# SCH_Power_Jack.net
KiCad netlist of a schematic drawn in Altium Designer
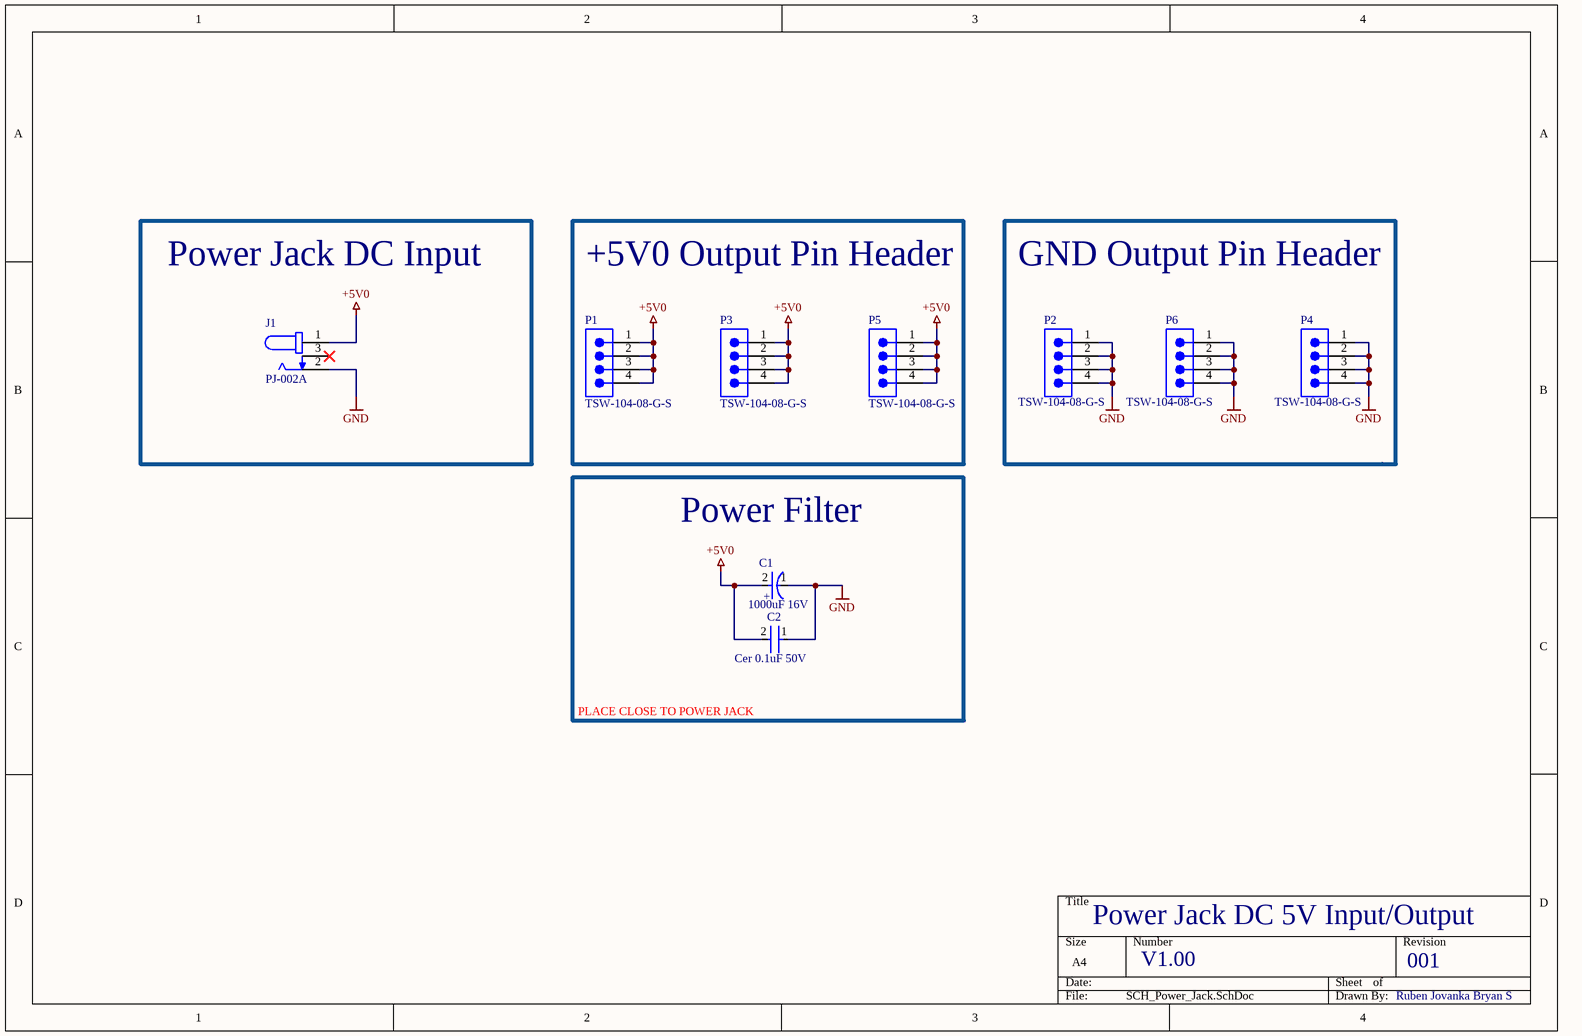
[diagram p0: SCH_Power_Jack.SchDoc]

(export (version "E")
  (design (tool "Eeschema 10.0.6"))
  (components
    (comp (ref "C1")
      (value "1000uF 16V")
      (footprint "FP-OS-CON-SMT-F10-MFG")
      (description "CAP ALUM POLY 1000UF 20% 16V SMD")
      (libsource (lib "Altium Content Vault") (part "203bc49f2ac43e59fd269a8c329ed05"))
    )
    (comp (ref "C2")
      (value "Cer 0.1uF 50V")
      (footprint "FP-K15H5-MFG")
      (description "CAP CER 0.1UF 50V X7R RADIAL")
      (fields (field (name "TOLERANCE") "10%") (field (name "VOLTAGE") "50V"))
      (libsource (lib "Altium Content Vault") (part "02cd4be3c70576c341d710602a673aa"))
    )
    (comp (ref "J1")
      (value "PJ-002A")
      (footprint "CUI_PJ-002A")
      (description "2.0 x 6.5 mm, 2.5 A, Horizontal, Through Hole, Dc Power Jack Connector")
      (fields (field (name "MF") "Same Sky"))
      (libsource (lib "PJ-002A") (part "PJ-002A"))
    )
    (comp (ref "P1")
      (value "TSW-104-08-G-S")
      (footprint "SMTC-TSW-104-08-X-S")
      (description "0.025\" SQ Post Header, Through-hole, Vertical, -55 to 125 degC, 2.54 mm Pitch, 4-Pin, Male, RoHS")
      (fields (field (name "MANUFACTURER") "Samtec"))
      (libsource (lib "Altium Content Vault") (part "SMTC-TSW-104-08-X-S"))
    )
    (comp (ref "P2")
      (value "TSW-104-08-G-S")
      (footprint "SMTC-TSW-104-08-X-S")
      (description "0.025\" SQ Post Header, Through-hole, Vertical, -55 to 125 degC, 2.54 mm Pitch, 4-Pin, Male, RoHS")
      (fields (field (name "MANUFACTURER") "Samtec"))
      (libsource (lib "Altium Content Vault") (part "SMTC-TSW-104-08-X-S"))
    )
    (comp (ref "P3")
      (value "TSW-104-08-G-S")
      (footprint "SMTC-TSW-104-08-X-S")
      (description "0.025\" SQ Post Header, Through-hole, Vertical, -55 to 125 degC, 2.54 mm Pitch, 4-Pin, Male, RoHS")
      (fields (field (name "MANUFACTURER") "Samtec"))
      (libsource (lib "Altium Content Vault") (part "SMTC-TSW-104-08-X-S"))
    )
    (comp (ref "P4")
      (value "TSW-104-08-G-S")
      (footprint "SMTC-TSW-104-08-X-S")
      (description "0.025\" SQ Post Header, Through-hole, Vertical, -55 to 125 degC, 2.54 mm Pitch, 4-Pin, Male, RoHS")
      (fields (field (name "MANUFACTURER") "Samtec"))
      (libsource (lib "Altium Content Vault") (part "SMTC-TSW-104-08-X-S"))
    )
    (comp (ref "P5")
      (value "TSW-104-08-G-S")
      (footprint "SMTC-TSW-104-08-X-S")
      (description "0.025\" SQ Post Header, Through-hole, Vertical, -55 to 125 degC, 2.54 mm Pitch, 4-Pin, Male, RoHS")
      (fields (field (name "MANUFACTURER") "Samtec"))
      (libsource (lib "Altium Content Vault") (part "SMTC-TSW-104-08-X-S"))
    )
    (comp (ref "P6")
      (value "TSW-104-08-G-S")
      (footprint "SMTC-TSW-104-08-X-S")
      (description "0.025\" SQ Post Header, Through-hole, Vertical, -55 to 125 degC, 2.54 mm Pitch, 4-Pin, Male, RoHS")
      (fields (field (name "MANUFACTURER") "Samtec"))
      (libsource (lib "Altium Content Vault") (part "SMTC-TSW-104-08-X-S"))
    )
  )
  (nets
    (net (code "1") (name "+5V0") (class "Default")
      (node (ref "C1") (pin "2") (pinfunction "A_2") (pintype "passive"))
      (node (ref "C2") (pin "2") (pinfunction "2_2") (pintype "passive"))
      (node (ref "J1") (pin "1") (pinfunction "1_1") (pintype "passive"))
      (node (ref "P1") (pin "1") (pinfunction "1_1") (pintype "passive"))
      (node (ref "P1") (pin "2") (pinfunction "2_2") (pintype "passive"))
      (node (ref "P1") (pin "3") (pinfunction "3_3") (pintype "passive"))
      (node (ref "P1") (pin "4") (pinfunction "4_4") (pintype "passive"))
      (node (ref "P3") (pin "1") (pinfunction "1_1") (pintype "passive"))
      (node (ref "P3") (pin "2") (pinfunction "2_2") (pintype "passive"))
      (node (ref "P3") (pin "3") (pinfunction "3_3") (pintype "passive"))
      (node (ref "P3") (pin "4") (pinfunction "4_4") (pintype "passive"))
      (node (ref "P5") (pin "1") (pinfunction "1_1") (pintype "passive"))
      (node (ref "P5") (pin "2") (pinfunction "2_2") (pintype "passive"))
      (node (ref "P5") (pin "3") (pinfunction "3_3") (pintype "passive"))
      (node (ref "P5") (pin "4") (pinfunction "4_4") (pintype "passive"))
    )
    (net (code "2") (name "GND") (class "Default")
      (node (ref "C1") (pin "1") (pinfunction "C_1") (pintype "passive"))
      (node (ref "C2") (pin "1") (pinfunction "1_1") (pintype "passive"))
      (node (ref "J1") (pin "2") (pinfunction "2_2") (pintype "passive"))
      (node (ref "P2") (pin "1") (pinfunction "1_1") (pintype "passive"))
      (node (ref "P2") (pin "2") (pinfunction "2_2") (pintype "passive"))
      (node (ref "P2") (pin "3") (pinfunction "3_3") (pintype "passive"))
      (node (ref "P2") (pin "4") (pinfunction "4_4") (pintype "passive"))
      (node (ref "P4") (pin "1") (pinfunction "1_1") (pintype "passive"))
      (node (ref "P4") (pin "2") (pinfunction "2_2") (pintype "passive"))
      (node (ref "P4") (pin "3") (pinfunction "3_3") (pintype "passive"))
      (node (ref "P4") (pin "4") (pinfunction "4_4") (pintype "passive"))
      (node (ref "P6") (pin "1") (pinfunction "1_1") (pintype "passive"))
      (node (ref "P6") (pin "2") (pinfunction "2_2") (pintype "passive"))
      (node (ref "P6") (pin "3") (pinfunction "3_3") (pintype "passive"))
      (node (ref "P6") (pin "4") (pinfunction "4_4") (pintype "passive"))
    )
    (net (code "3") (name "unconnected-(J1-Pad3)") (class "Default")
      (node (ref "J1") (pin "3") (pinfunction "3_3") (pintype "passive+no_connect"))
    )
  )
)
